# SCH_Master.net
KiCad netlist of a schematic drawn in Altium Designer
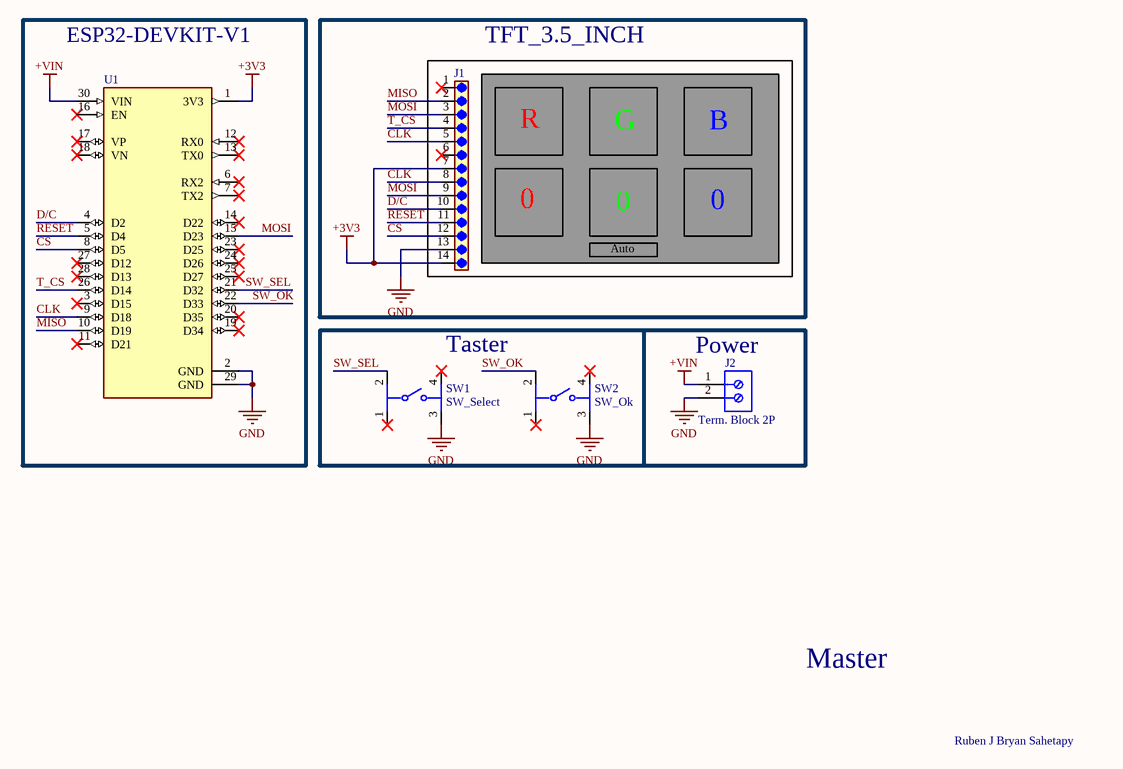
[diagram p0: SCH_Master.SchDoc]

(export (version "E")
  (design (tool "Eeschema 10.0.6"))
  (components
    (comp (ref "J1")
      (value "TFT_3.5_INCH")
      (footprint "61301411121")
      (description "3.5-inch TFT LCD (320 × 480) with ILI9488 driver + XPT2046 resistive touch")
      (fields (field (name "MF") "WÃ¼rth Elektronik") (field (name "MP") "61301411121"))
      (libsource (lib "MarbleLib") (part "TFT_3.5_INCH"))
    )
    (comp (ref "J2")
      (value "Term. Block 2P")
      (footprint "691253410002")
      (description "Terminal Block, 7.62MM Pitch, Horizontal, Rising Cage Clamp, 12-30 AWG, 2 Pin")
      (libsource (lib "Altium Content Vault") (part "TBL - 1R - 02P - Screw"))
    )
    (comp (ref "SW1")
      (value "SW_Select")
      (footprint "FP-MJTP1212A-MFG")
      (description "Switch Tactile Button 12x12mm")
      (fields (field (name "PART NUMBER") "MJTP1212A"))
      (libsource (lib "MarbleLib") (part "CMP-47024-000003-1"))
    )
    (comp (ref "SW2")
      (value "SW_Ok")
      (footprint "FP-MJTP1212A-MFG")
      (description "Switch Tactile Button 12x12mm")
      (fields (field (name "PART NUMBER") "MJTP1212A"))
      (libsource (lib "MarbleLib") (part "CMP-47024-000003-1"))
    )
    (comp (ref "U1")
      (value "ESP32-DEVKIT-V1")
      (footprint "MODULE_ESP32_DEVKIT_V1")
      (description "ESP32-DEVKIT-V1 30 Pins")
      (fields (field (name "MF") "Do it"))
      (libsource (lib "MarbleLib") (part "ESP32-DEVKIT-V1"))
    )
  )
  (nets
    (net (code "1") (name "+3V3") (class "Default")
      (node (ref "J1") (pin "14") (pinfunction "14_14") (pintype "passive"))
      (node (ref "J1") (pin "7") (pinfunction "7_7") (pintype "passive"))
      (node (ref "U1") (pin "1") (pinfunction "3V3_1") (pintype "output"))
    )
    (net (code "2") (name "+VIN") (class "Default")
      (node (ref "J2") (pin "1") (pinfunction "1_1") (pintype "passive"))
      (node (ref "U1") (pin "30") (pinfunction "VIN_30") (pintype "input"))
    )
    (net (code "3") (name "/CLK") (class "Default")
      (node (ref "J1") (pin "5") (pinfunction "5_5") (pintype "passive"))
      (node (ref "J1") (pin "8") (pinfunction "8_8") (pintype "passive"))
      (node (ref "U1") (pin "9") (pinfunction "D18_9") (pintype "bidirectional"))
    )
    (net (code "4") (name "/CS") (class "Default")
      (node (ref "J1") (pin "12") (pinfunction "12_12") (pintype "passive"))
      (node (ref "U1") (pin "8") (pinfunction "D5_8") (pintype "bidirectional"))
    )
    (net (code "5") (name "/D{slash}C") (class "Default")
      (node (ref "J1") (pin "10") (pinfunction "10_10") (pintype "passive"))
      (node (ref "U1") (pin "4") (pinfunction "D2_4") (pintype "bidirectional"))
    )
    (net (code "6") (name "/MISO") (class "Default")
      (node (ref "J1") (pin "2") (pinfunction "2_2") (pintype "passive"))
      (node (ref "U1") (pin "10") (pinfunction "D19_10") (pintype "bidirectional"))
    )
    (net (code "7") (name "/MOSI") (class "Default")
      (node (ref "J1") (pin "3") (pinfunction "3_3") (pintype "passive"))
      (node (ref "J1") (pin "9") (pinfunction "9_9") (pintype "passive"))
      (node (ref "U1") (pin "15") (pinfunction "D23_15") (pintype "bidirectional"))
    )
    (net (code "8") (name "/RESET") (class "Default")
      (node (ref "J1") (pin "11") (pinfunction "11_11") (pintype "passive"))
      (node (ref "U1") (pin "5") (pinfunction "D4_5") (pintype "bidirectional"))
    )
    (net (code "9") (name "/SW_OK") (class "Default")
      (node (ref "SW2") (pin "2") (pinfunction "2_2") (pintype "passive"))
      (node (ref "U1") (pin "22") (pinfunction "D33_22") (pintype "bidirectional"))
    )
    (net (code "10") (name "/SW_SEL") (class "Default")
      (node (ref "SW1") (pin "2") (pinfunction "2_2") (pintype "passive"))
      (node (ref "U1") (pin "21") (pinfunction "D32_21") (pintype "bidirectional"))
    )
    (net (code "11") (name "/T_CS") (class "Default")
      (node (ref "J1") (pin "4") (pinfunction "4_4") (pintype "passive"))
      (node (ref "U1") (pin "26") (pinfunction "D14_26") (pintype "bidirectional"))
    )
    (net (code "12") (name "GND") (class "Default")
      (node (ref "J1") (pin "13") (pinfunction "13_13") (pintype "passive"))
      (node (ref "J2") (pin "2") (pinfunction "2_2") (pintype "passive"))
      (node (ref "SW1") (pin "3") (pinfunction "3_3") (pintype "passive"))
      (node (ref "SW2") (pin "3") (pinfunction "3_3") (pintype "passive"))
      (node (ref "U1") (pin "2") (pinfunction "GND_2") (pintype "power_in"))
      (node (ref "U1") (pin "29") (pinfunction "GND_29") (pintype "power_in"))
    )
    (net (code "13") (name "unconnected-(J1-Pad1)") (class "Default")
      (node (ref "J1") (pin "1") (pinfunction "1_1") (pintype "passive+no_connect"))
    )
    (net (code "14") (name "unconnected-(J1-Pad6)") (class "Default")
      (node (ref "J1") (pin "6") (pinfunction "6_6") (pintype "passive+no_connect"))
    )
    (net (code "15") (name "unconnected-(SW1-Pad1)") (class "Default")
      (node (ref "SW1") (pin "1") (pinfunction "1_1") (pintype "passive+no_connect"))
    )
    (net (code "16") (name "unconnected-(SW1-Pad4)") (class "Default")
      (node (ref "SW1") (pin "4") (pinfunction "4_4") (pintype "passive+no_connect"))
    )
    (net (code "17") (name "unconnected-(SW2-Pad1)") (class "Default")
      (node (ref "SW2") (pin "1") (pinfunction "1_1") (pintype "passive+no_connect"))
    )
    (net (code "18") (name "unconnected-(SW2-Pad4)") (class "Default")
      (node (ref "SW2") (pin "4") (pinfunction "4_4") (pintype "passive+no_connect"))
    )
    (net (code "19") (name "unconnected-(U1-D12-Pad27)") (class "Default")
      (node (ref "U1") (pin "27") (pinfunction "D12_27") (pintype "bidirectional+no_connect"))
    )
    (net (code "20") (name "unconnected-(U1-D13-Pad28)") (class "Default")
      (node (ref "U1") (pin "28") (pinfunction "D13_28") (pintype "bidirectional+no_connect"))
    )
    (net (code "21") (name "unconnected-(U1-D15-Pad3)") (class "Default")
      (node (ref "U1") (pin "3") (pinfunction "D15_3") (pintype "bidirectional+no_connect"))
    )
    (net (code "22") (name "unconnected-(U1-D21-Pad11)") (class "Default")
      (node (ref "U1") (pin "11") (pinfunction "D21_11") (pintype "bidirectional+no_connect"))
    )
    (net (code "23") (name "unconnected-(U1-D22-Pad14)") (class "Default")
      (node (ref "U1") (pin "14") (pinfunction "D22_14") (pintype "bidirectional+no_connect"))
    )
    (net (code "24") (name "unconnected-(U1-D25-Pad23)") (class "Default")
      (node (ref "U1") (pin "23") (pinfunction "D25_23") (pintype "bidirectional+no_connect"))
    )
    (net (code "25") (name "unconnected-(U1-D26-Pad24)") (class "Default")
      (node (ref "U1") (pin "24") (pinfunction "D26_24") (pintype "bidirectional+no_connect"))
    )
    (net (code "26") (name "unconnected-(U1-D27-Pad25)") (class "Default")
      (node (ref "U1") (pin "25") (pinfunction "D27_25") (pintype "bidirectional+no_connect"))
    )
    (net (code "27") (name "unconnected-(U1-D34-Pad19)") (class "Default")
      (node (ref "U1") (pin "19") (pinfunction "D34_19") (pintype "bidirectional+no_connect"))
    )
    (net (code "28") (name "unconnected-(U1-D35-Pad20)") (class "Default")
      (node (ref "U1") (pin "20") (pinfunction "D35_20") (pintype "bidirectional+no_connect"))
    )
    (net (code "29") (name "unconnected-(U1-EN-Pad16)") (class "Default")
      (node (ref "U1") (pin "16") (pinfunction "EN_16") (pintype "input+no_connect"))
    )
    (net (code "30") (name "unconnected-(U1-RX0-Pad12)") (class "Default")
      (node (ref "U1") (pin "12") (pinfunction "RX0_12") (pintype "input+no_connect"))
    )
    (net (code "31") (name "unconnected-(U1-RX2-Pad6)") (class "Default")
      (node (ref "U1") (pin "6") (pinfunction "RX2_6") (pintype "input+no_connect"))
    )
    (net (code "32") (name "unconnected-(U1-TX0-Pad13)") (class "Default")
      (node (ref "U1") (pin "13") (pinfunction "TX0_13") (pintype "output+no_connect"))
    )
    (net (code "33") (name "unconnected-(U1-TX2-Pad7)") (class "Default")
      (node (ref "U1") (pin "7") (pinfunction "TX2_7") (pintype "output+no_connect"))
    )
    (net (code "34") (name "unconnected-(U1-VN-Pad18)") (class "Default")
      (node (ref "U1") (pin "18") (pinfunction "VN_18") (pintype "bidirectional+no_connect"))
    )
    (net (code "35") (name "unconnected-(U1-VP-Pad17)") (class "Default")
      (node (ref "U1") (pin "17") (pinfunction "VP_17") (pintype "bidirectional+no_connect"))
    )
  )
)
